# Ampli3.net
KiCad netlist of a schematic drawn in Altium Designer
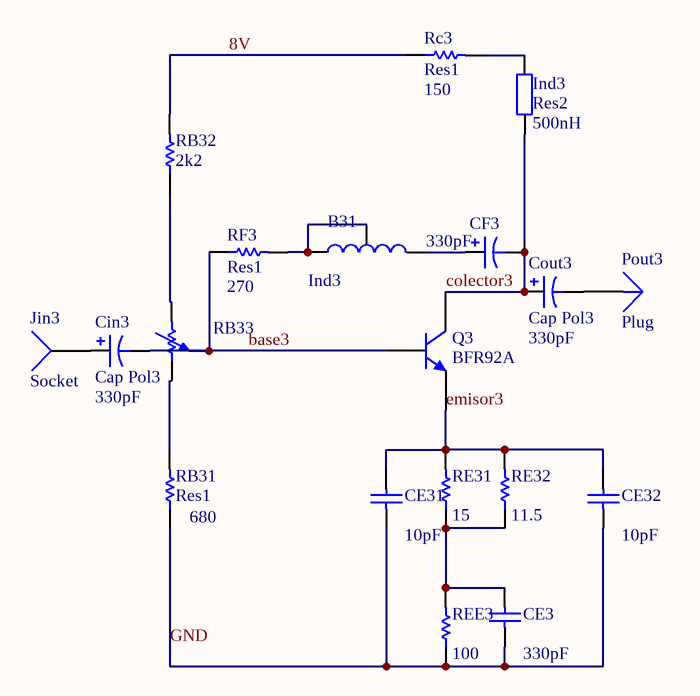
[diagram p0: Ampli3.SchDoc]

(export (version "E")
  (design (tool "Eeschema 10.0.6"))
  (components
    (comp (ref "B31") (value "Ind3") (footprint "Ind 7mm") (libsource (lib "epf") (part "Ind3")))
    (comp (ref "CE3")
      (value "330pF")
      (footprint "1608[0603]")
      (description "Capacitor (Semiconductor SIM Model)")
      (fields (field (name "Comment") "Cap Semi") (field (name "PUBLISHER") "Altium Limited"))
      (libsource (lib "Miscellaneous Devices") (part "Cap Semi"))
    )
    (comp (ref "CE31")
      (value "10pF")
      (footprint "1608[0603]")
      (description "Capacitor (Semiconductor SIM Model)")
      (fields (field (name "Comment") "Cap Semi") (field (name "PUBLISHER") "Altium Limited"))
      (libsource (lib "Miscellaneous Devices") (part "Cap Semi"))
    )
    (comp (ref "CE32")
      (value "10pF")
      (footprint "1608[0603]")
      (description "Capacitor (Semiconductor SIM Model)")
      (fields (field (name "Comment") "Cap Semi") (field (name "PUBLISHER") "Altium Limited"))
      (libsource (lib "Miscellaneous Devices") (part "Cap Semi"))
    )
    (comp (ref "CF3")
      (value "330pF")
      (footprint "C0805")
      (description "Polarized Capacitor (Surface Mount)")
      (fields (field (name "Comment") "Cap Pol3") (field (name "PUBLISHER") "Altium Limited"))
      (libsource (lib "Miscellaneous Devices") (part "Cap Pol3"))
    )
    (comp (ref "Cin3")
      (value "Cap Pol3")
      (footprint "C0805")
      (description "Polarized Capacitor (Surface Mount)")
      (fields (field (name "ALTIUM_VALUE") "330pF") (field (name "PUBLISHER") "Altium Limited"))
      (libsource (lib "Miscellaneous Devices") (part "Cap Pol3"))
    )
    (comp (ref "Cout3")
      (value "Cap Pol3")
      (footprint "C0805")
      (description "Polarized Capacitor (Surface Mount)")
      (fields (field (name "ALTIUM_VALUE") "330pF") (field (name "PUBLISHER") "Altium Limited"))
      (libsource (lib "Miscellaneous Devices") (part "Cap Pol3"))
    )
    (comp (ref "Ind3")
      (value "Res2")
      (footprint "AXIAL-0.4")
      (description "Resistor")
      (fields (field (name "ALTIUM_VALUE") "500nH") (field (name "PUBLISHER") "Altium Limited"))
      (libsource (lib "Miscellaneous Devices") (part "Res2"))
    )
    (comp (ref "Jin3")
      (value "Socket")
      (footprint "PIN1")
      (fields (field (name "PUBLISHER") "Altium Limited"))
      (libsource (lib "Miscellaneous Connectors") (part "Socket"))
    )
    (comp (ref "Pout3")
      (value "Plug")
      (footprint "PIN1")
      (fields (field (name "PUBLISHER") "Altium Limited"))
      (libsource (lib "Miscellaneous Connectors") (part "Plug"))
    )
    (comp (ref "Q3")
      (value "BFR92A")
      (footprint "SOT23")
      (description "NPN 5 GHz Wideband Transistor")
      (fields (field (name "PUBLISHER") "Altium Limited"))
      (libsource (lib "Philips Discrete BJT - RF Transistor") (part "BFR92A"))
    )
    (comp (ref "RB31")
      (value "Res1")
      (footprint "AXIAL-0.3")
      (description "Resistor")
      (fields (field (name "ALTIUM_VALUE") "680") (field (name "PUBLISHER") "Altium Limited"))
      (libsource (lib "Miscellaneous Devices") (part "Res1"))
    )
    (comp (ref "RB32")
      (value "2k2")
      (footprint "AXIAL-0.3")
      (description "Resistor")
      (fields (field (name "Comment") "Res1") (field (name "PUBLISHER") "Altium Limited"))
      (libsource (lib "Miscellaneous Devices") (part "Res1"))
    )
    (comp (ref "RB33") (value "Pot") (footprint "Potenciometro") (libsource (lib "epf") (part "Pot")))
    (comp (ref "Rc3")
      (value "Res1")
      (footprint "AXIAL-0.3")
      (description "Resistor")
      (fields (field (name "ALTIUM_VALUE") "150") (field (name "PUBLISHER") "Altium Limited"))
      (libsource (lib "Miscellaneous Devices") (part "Res1"))
    )
    (comp (ref "RE31")
      (value "15")
      (footprint "1608[0603]")
      (description "Semiconductor Resistor")
      (fields (field (name "Comment") "Res Semi") (field (name "PUBLISHER") "Altium Limited"))
      (libsource (lib "Miscellaneous Devices") (part "Res Semi"))
    )
    (comp (ref "RE32")
      (value "11.5")
      (footprint "2012[0805]")
      (description "Semiconductor Resistor")
      (fields (field (name "Comment") "Res Semi") (field (name "PUBLISHER") "Altium Limited"))
      (libsource (lib "Miscellaneous Devices") (part "Res Semi"))
    )
    (comp (ref "REE3")
      (value "100")
      (footprint "2012[0805]")
      (description "Semiconductor Resistor")
      (fields (field (name "Comment") "Res Semi") (field (name "PUBLISHER") "Altium Limited"))
      (libsource (lib "Miscellaneous Devices") (part "Res Semi"))
    )
    (comp (ref "RF3")
      (value "Res1")
      (footprint "AXIAL-0.3")
      (description "Resistor")
      (fields (field (name "ALTIUM_VALUE") "270") (field (name "PUBLISHER") "Altium Limited"))
      (libsource (lib "Miscellaneous Devices") (part "Res1"))
    )
  )
  (nets
    (net (code "1") (name "/8V") (class "Default")
      (node (ref "RB32") (pin "2") (pinfunction "2_2") (pintype "passive"))
      (node (ref "Rc3") (pin "1") (pinfunction "1_1") (pintype "passive"))
    )
    (net (code "2") (name "/GND") (class "Default")
      (node (ref "CE3") (pin "1") (pinfunction "1_1") (pintype "passive"))
      (node (ref "CE31") (pin "1") (pinfunction "1_1") (pintype "passive"))
      (node (ref "CE32") (pin "1") (pinfunction "1_1") (pintype "passive"))
      (node (ref "RB31") (pin "1") (pinfunction "1_1") (pintype "passive"))
      (node (ref "REE3") (pin "1") (pinfunction "1_1") (pintype "passive"))
    )
    (net (code "3") (name "/base3") (class "Default")
      (node (ref "Cin3") (pin "2") (pinfunction "2_2") (pintype "passive"))
      (node (ref "Q3") (pin "1") (pinfunction "B_1") (pintype "passive"))
      (node (ref "RB33") (pin "3") (pinfunction "3_3") (pintype "passive"))
      (node (ref "RF3") (pin "1") (pinfunction "1_1") (pintype "passive"))
    )
    (net (code "4") (name "/colector3") (class "Default")
      (node (ref "CF3") (pin "2") (pinfunction "2_2") (pintype "passive"))
      (node (ref "Cout3") (pin "1") (pinfunction "1_1") (pintype "passive"))
      (node (ref "Ind3") (pin "1") (pinfunction "1_1") (pintype "passive"))
      (node (ref "Q3") (pin "3") (pinfunction "C_3") (pintype "passive"))
    )
    (net (code "5") (name "/emisor3") (class "Default")
      (node (ref "CE31") (pin "2") (pinfunction "2_2") (pintype "passive"))
      (node (ref "CE32") (pin "2") (pinfunction "2_2") (pintype "passive"))
      (node (ref "Q3") (pin "2") (pinfunction "E_2") (pintype "passive"))
      (node (ref "RE31") (pin "2") (pinfunction "2_2") (pintype "passive"))
      (node (ref "RE32") (pin "2") (pinfunction "2_2") (pintype "passive"))
    )
    (net (code "6") (name "Net-(B31-Pad0)") (class "Default")
      (node (ref "B31") (pin "0") (pinfunction "0_0") (pintype "passive"))
      (node (ref "B31") (pin "2") (pinfunction "2_2") (pintype "passive"))
      (node (ref "RF3") (pin "2") (pinfunction "2_2") (pintype "passive"))
    )
    (net (code "7") (name "Net-(B31-Pad1)") (class "Default")
      (node (ref "B31") (pin "1") (pinfunction "1_1") (pintype "passive"))
      (node (ref "CF3") (pin "1") (pinfunction "1_1") (pintype "passive"))
    )
    (net (code "8") (name "Net-(CE3-Pad2)") (class "Default")
      (node (ref "CE3") (pin "2") (pinfunction "2_2") (pintype "passive"))
      (node (ref "RE31") (pin "1") (pinfunction "1_1") (pintype "passive"))
      (node (ref "RE32") (pin "1") (pinfunction "1_1") (pintype "passive"))
      (node (ref "REE3") (pin "2") (pinfunction "2_2") (pintype "passive"))
    )
    (net (code "9") (name "Net-(Cin3-Pad1)") (class "Default")
      (node (ref "Cin3") (pin "1") (pinfunction "1_1") (pintype "passive"))
      (node (ref "Jin3") (pin "1") (pinfunction "1_1") (pintype "passive"))
    )
    (net (code "10") (name "Net-(Cout3-Pad2)") (class "Default")
      (node (ref "Cout3") (pin "2") (pinfunction "2_2") (pintype "passive"))
      (node (ref "Pout3") (pin "1") (pinfunction "1_1") (pintype "passive"))
    )
    (net (code "11") (name "Net-(Ind3-Pad2)") (class "Default")
      (node (ref "Ind3") (pin "2") (pinfunction "2_2") (pintype "passive"))
      (node (ref "Rc3") (pin "2") (pinfunction "2_2") (pintype "passive"))
    )
    (net (code "12") (name "Net-(RB31-Pad2)") (class "Default")
      (node (ref "RB31") (pin "2") (pinfunction "2_2") (pintype "passive"))
      (node (ref "RB33") (pin "2") (pinfunction "2_2") (pintype "passive"))
    )
    (net (code "13") (name "Net-(RB32-Pad1)") (class "Default")
      (node (ref "RB32") (pin "1") (pinfunction "1_1") (pintype "passive"))
      (node (ref "RB33") (pin "1") (pinfunction "1_1") (pintype "passive"))
    )
  )
)
